# zero_board.net
KiCad netlist of a schematic drawn in EAGLE
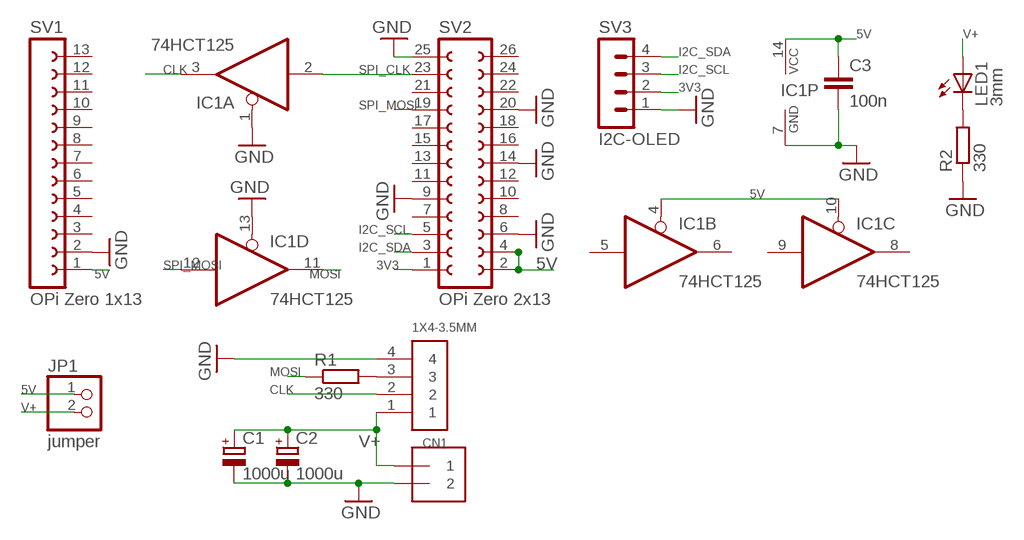
[diagram p0: schematic, sheet 1]

(export (version "E")
  (design (tool "Eeschema 10.0.6"))
  (components
    (comp (ref "C1")
      (value "1000u")
      (footprint "eagle-import:E5-6")
      (libsource (lib "eagle-import") (part "CPOL-EUE5-6"))
    )
    (comp (ref "C2")
      (value "1000u")
      (footprint "eagle-import:E5-6")
      (libsource (lib "eagle-import") (part "CPOL-EUE5-6"))
    )
    (comp (ref "C3")
      (value "100n")
      (footprint "eagle-import:C050-024X044")
      (libsource (lib "eagle-import") (part "C-EU050-024X044"))
    )
    (comp (ref "CN1")
      (value "1X4-3.5MM")
      (footprint "eagle-import:1X04-3.5MM")
      (libsource (lib "eagle-import") (part "1X4-3.5MM"))
    )
    (comp (ref "IC1")
      (value "74HCT125")
      (footprint "eagle-import:DIL14")
      (libsource (lib "eagle-import") (part "74125NHCT"))
    )
    (comp (ref "J1")
      (value "1X2-3.5MM")
      (footprint "eagle-import:1X2-3.5MM")
      (libsource (lib "eagle-import") (part "1X2-3.5MM"))
    )
    (comp (ref "JP1")
      (value "jumper")
      (footprint "eagle-import:1X02")
      (libsource (lib "eagle-import") (part "PINHD-1X2"))
    )
    (comp (ref "LED1")
      (value "3mm")
      (footprint "eagle-import:LED3MM")
      (libsource (lib "eagle-import") (part "LED3MM"))
    )
    (comp (ref "R1")
      (value "330")
      (footprint "eagle-import:0204_7")
      (libsource (lib "eagle-import") (part "R-EU_0204/7"))
    )
    (comp (ref "R2")
      (value "330")
      (footprint "eagle-import:0204_7")
      (libsource (lib "eagle-import") (part "R-EU_0204/7"))
    )
    (comp (ref "SV1")
      (value "OPi Zero 1x13")
      (footprint "eagle-import:FE13")
      (libsource (lib "eagle-import") (part "FE13-1"))
    )
    (comp (ref "SV2")
      (value "OPi Zero 2x13")
      (footprint "eagle-import:FE13-2")
      (libsource (lib "eagle-import") (part "FE13-2"))
    )
    (comp (ref "SV3")
      (value "I2C-OLED")
      (footprint "eagle-import:MA04-1")
      (libsource (lib "eagle-import") (part "MA04-1"))
    )
  )
  (nets
    (net (code "1") (name "/3V3") (class "Default")
      (node (ref "SV2") (pin "1") (pinfunction "1_1") (pintype "passive"))
      (node (ref "SV3") (pin "2") (pinfunction "2_2") (pintype "passive"))
    )
    (net (code "2") (name "/5V") (class "Default")
      (node (ref "C3") (pin "1") (pinfunction "1_1") (pintype "passive"))
      (node (ref "IC1") (pin "10") (pinfunction "OE_10") (pintype "input"))
      (node (ref "IC1") (pin "14") (pinfunction "VCC_14") (pintype "power_in"))
      (node (ref "IC1") (pin "4") (pinfunction "OE_4") (pintype "input"))
      (node (ref "JP1") (pin "1") (pinfunction "1_1") (pintype "passive"))
      (node (ref "SV1") (pin "1") (pinfunction "1_1") (pintype "passive"))
      (node (ref "SV2") (pin "2") (pinfunction "2_2") (pintype "passive"))
      (node (ref "SV2") (pin "4") (pinfunction "4_4") (pintype "passive"))
    )
    (net (code "3") (name "/CLK") (class "Default")
      (node (ref "CN1") (pin "2") (pinfunction "2_2") (pintype "bidirectional"))
      (node (ref "IC1") (pin "3") (pinfunction "O_3") (pintype "tri_state"))
    )
    (net (code "4") (name "/I2C_SCL") (class "Default")
      (node (ref "SV2") (pin "5") (pinfunction "5_5") (pintype "passive"))
      (node (ref "SV3") (pin "3") (pinfunction "3_3") (pintype "passive"))
    )
    (net (code "5") (name "/I2C_SDA") (class "Default")
      (node (ref "SV2") (pin "3") (pinfunction "3_3") (pintype "passive"))
      (node (ref "SV3") (pin "4") (pinfunction "4_4") (pintype "passive"))
    )
    (net (code "6") (name "/MOSI") (class "Default")
      (node (ref "IC1") (pin "11") (pinfunction "O_11") (pintype "tri_state"))
      (node (ref "R1") (pin "1") (pinfunction "1_1") (pintype "passive"))
    )
    (net (code "7") (name "/SPI_CLK") (class "Default")
      (node (ref "IC1") (pin "2") (pinfunction "I_2") (pintype "input"))
      (node (ref "SV2") (pin "23") (pinfunction "23_23") (pintype "passive"))
    )
    (net (code "8") (name "/SPI_MOSI") (class "Default")
      (node (ref "IC1") (pin "12") (pinfunction "I_12") (pintype "input"))
      (node (ref "SV2") (pin "19") (pinfunction "19_19") (pintype "passive"))
    )
    (net (code "9") (name "/V+") (class "Default")
      (node (ref "C1") (pin "+") (pinfunction "+_+") (pintype "passive"))
      (node (ref "C2") (pin "+") (pinfunction "+_+") (pintype "passive"))
      (node (ref "CN1") (pin "1") (pinfunction "1_1") (pintype "bidirectional"))
      (node (ref "J1") (pin "1") (pinfunction "1_1") (pintype "passive"))
      (node (ref "JP1") (pin "2") (pinfunction "2_2") (pintype "passive"))
      (node (ref "LED1") (pin "A") (pinfunction "A_A") (pintype "passive"))
    )
    (net (code "10") (name "GND") (class "Default")
      (node (ref "C1") (pin "-") (pinfunction "-_-") (pintype "passive"))
      (node (ref "C2") (pin "-") (pinfunction "-_-") (pintype "passive"))
      (node (ref "C3") (pin "2") (pinfunction "2_2") (pintype "passive"))
      (node (ref "CN1") (pin "4") (pinfunction "4_4") (pintype "bidirectional"))
      (node (ref "IC1") (pin "1") (pinfunction "OE_1") (pintype "input"))
      (node (ref "IC1") (pin "13") (pinfunction "OE_13") (pintype "input"))
      (node (ref "IC1") (pin "7") (pinfunction "GND_7") (pintype "power_in"))
      (node (ref "J1") (pin "2") (pinfunction "2_2") (pintype "passive"))
      (node (ref "R2") (pin "1") (pinfunction "1_1") (pintype "passive"))
      (node (ref "SV1") (pin "2") (pinfunction "2_2") (pintype "passive"))
      (node (ref "SV2") (pin "14") (pinfunction "14_14") (pintype "passive"))
      (node (ref "SV2") (pin "20") (pinfunction "20_20") (pintype "passive"))
      (node (ref "SV2") (pin "25") (pinfunction "25_25") (pintype "passive"))
      (node (ref "SV2") (pin "6") (pinfunction "6_6") (pintype "passive"))
      (node (ref "SV2") (pin "9") (pinfunction "9_9") (pintype "passive"))
      (node (ref "SV3") (pin "1") (pinfunction "1_1") (pintype "passive"))
    )
    (net (code "11") (name "Net-(CN1-Pad3)") (class "Default")
      (node (ref "CN1") (pin "3") (pinfunction "3_3") (pintype "bidirectional"))
      (node (ref "R1") (pin "2") (pinfunction "2_2") (pintype "passive"))
    )
    (net (code "12") (name "Net-(LED1-C)") (class "Default")
      (node (ref "LED1") (pin "K") (pinfunction "C_K") (pintype "passive"))
      (node (ref "R2") (pin "2") (pinfunction "2_2") (pintype "passive"))
    )
    (net (code "13") (name "unconnected-(IC1B-I-Pad5)") (class "Default")
      (node (ref "IC1") (pin "5") (pinfunction "I_5") (pintype "input"))
    )
    (net (code "14") (name "unconnected-(IC1B-O-Pad6)") (class "Default")
      (node (ref "IC1") (pin "6") (pinfunction "O_6") (pintype "tri_state"))
    )
    (net (code "15") (name "unconnected-(IC1C-I-Pad9)") (class "Default")
      (node (ref "IC1") (pin "9") (pinfunction "I_9") (pintype "input"))
    )
    (net (code "16") (name "unconnected-(IC1C-O-Pad8)") (class "Default")
      (node (ref "IC1") (pin "8") (pinfunction "O_8") (pintype "tri_state"))
    )
    (net (code "17") (name "unconnected-(SV1-Pad3)") (class "Default")
      (node (ref "SV1") (pin "3") (pinfunction "3_3") (pintype "passive"))
    )
    (net (code "18") (name "unconnected-(SV1-Pad4)") (class "Default")
      (node (ref "SV1") (pin "4") (pinfunction "4_4") (pintype "passive"))
    )
    (net (code "19") (name "unconnected-(SV1-Pad5)") (class "Default")
      (node (ref "SV1") (pin "5") (pinfunction "5_5") (pintype "passive"))
    )
    (net (code "20") (name "unconnected-(SV1-Pad6)") (class "Default")
      (node (ref "SV1") (pin "6") (pinfunction "6_6") (pintype "passive"))
    )
    (net (code "21") (name "unconnected-(SV1-Pad7)") (class "Default")
      (node (ref "SV1") (pin "7") (pinfunction "7_7") (pintype "passive"))
    )
    (net (code "22") (name "unconnected-(SV1-Pad8)") (class "Default")
      (node (ref "SV1") (pin "8") (pinfunction "8_8") (pintype "passive"))
    )
    (net (code "23") (name "unconnected-(SV1-Pad9)") (class "Default")
      (node (ref "SV1") (pin "9") (pinfunction "9_9") (pintype "passive"))
    )
    (net (code "24") (name "unconnected-(SV1-Pad10)") (class "Default")
      (node (ref "SV1") (pin "10") (pinfunction "10_10") (pintype "passive"))
    )
    (net (code "25") (name "unconnected-(SV1-Pad11)") (class "Default")
      (node (ref "SV1") (pin "11") (pinfunction "11_11") (pintype "passive"))
    )
    (net (code "26") (name "unconnected-(SV1-Pad12)") (class "Default")
      (node (ref "SV1") (pin "12") (pinfunction "12_12") (pintype "passive"))
    )
    (net (code "27") (name "unconnected-(SV1-Pad13)") (class "Default")
      (node (ref "SV1") (pin "13") (pinfunction "13_13") (pintype "passive"))
    )
    (net (code "28") (name "unconnected-(SV2-Pad7)") (class "Default")
      (node (ref "SV2") (pin "7") (pinfunction "7_7") (pintype "passive"))
    )
    (net (code "29") (name "unconnected-(SV2-Pad8)") (class "Default")
      (node (ref "SV2") (pin "8") (pinfunction "8_8") (pintype "passive"))
    )
    (net (code "30") (name "unconnected-(SV2-Pad10)") (class "Default")
      (node (ref "SV2") (pin "10") (pinfunction "10_10") (pintype "passive"))
    )
    (net (code "31") (name "unconnected-(SV2-Pad11)") (class "Default")
      (node (ref "SV2") (pin "11") (pinfunction "11_11") (pintype "passive"))
    )
    (net (code "32") (name "unconnected-(SV2-Pad12)") (class "Default")
      (node (ref "SV2") (pin "12") (pinfunction "12_12") (pintype "passive"))
    )
    (net (code "33") (name "unconnected-(SV2-Pad13)") (class "Default")
      (node (ref "SV2") (pin "13") (pinfunction "13_13") (pintype "passive"))
    )
    (net (code "34") (name "unconnected-(SV2-Pad15)") (class "Default")
      (node (ref "SV2") (pin "15") (pinfunction "15_15") (pintype "passive"))
    )
    (net (code "35") (name "unconnected-(SV2-Pad16)") (class "Default")
      (node (ref "SV2") (pin "16") (pinfunction "16_16") (pintype "passive"))
    )
    (net (code "36") (name "unconnected-(SV2-Pad17)") (class "Default")
      (node (ref "SV2") (pin "17") (pinfunction "17_17") (pintype "passive"))
    )
    (net (code "37") (name "unconnected-(SV2-Pad18)") (class "Default")
      (node (ref "SV2") (pin "18") (pinfunction "18_18") (pintype "passive"))
    )
    (net (code "38") (name "unconnected-(SV2-Pad21)") (class "Default")
      (node (ref "SV2") (pin "21") (pinfunction "21_21") (pintype "passive"))
    )
    (net (code "39") (name "unconnected-(SV2-Pad22)") (class "Default")
      (node (ref "SV2") (pin "22") (pinfunction "22_22") (pintype "passive"))
    )
    (net (code "40") (name "unconnected-(SV2-Pad24)") (class "Default")
      (node (ref "SV2") (pin "24") (pinfunction "24_24") (pintype "passive"))
    )
    (net (code "41") (name "unconnected-(SV2-Pad26)") (class "Default")
      (node (ref "SV2") (pin "26") (pinfunction "26_26") (pintype "passive"))
    )
  )
)
